# LCD_Dev_SCH_1.net
KiCad netlist of a schematic drawn in Altium Designer
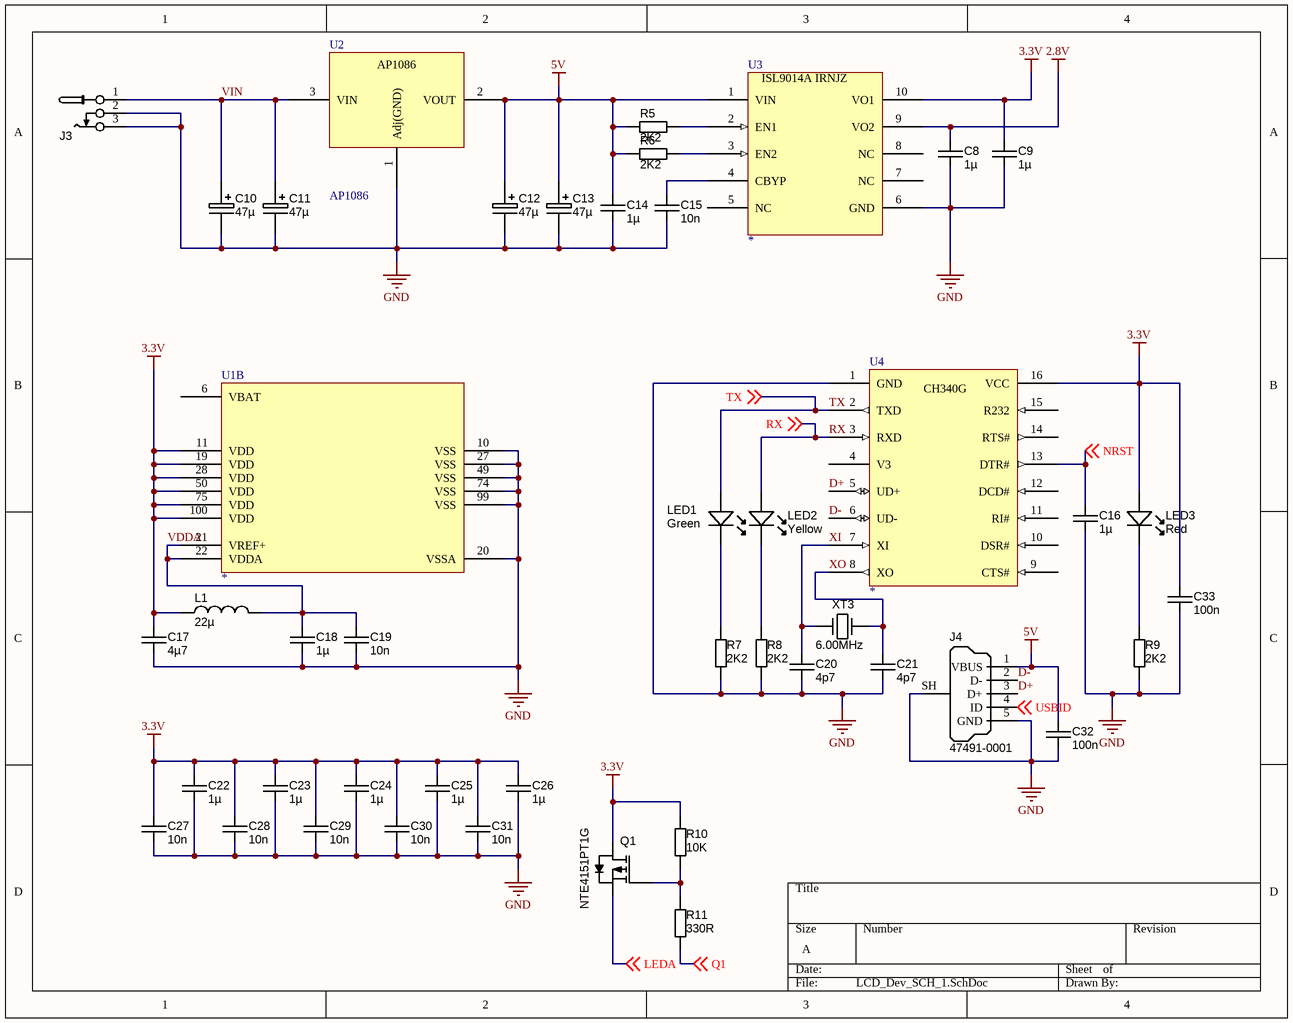
[diagram p0: LCD_Dev_SCH_1.SchDoc]

(export (version "E")
  (design (tool "Eeschema 10.0.6"))
  (components
    (comp (ref "C8")
      (value "1µ")
      (footprint "CAPC2012X135N")
      (description "Capacitor SMD Cer 1uF 10% 16V X7R 0805")
      (fields (field (name "TOLERANCE") "±10%") (field (name "Comment") "approved sub OK"))
      (libsource (lib "PBL - Capacitors") (part "CAPC_1u_0805_X7R_16V_10%"))
    )
    (comp (ref "C9")
      (value "1µ")
      (footprint "CAPC2012X135N")
      (description "Capacitor SMD Cer 1uF 10% 16V X7R 0805")
      (fields (field (name "TOLERANCE") "±10%") (field (name "Comment") "approved sub OK"))
      (libsource (lib "PBL - Capacitors") (part "CAPC_1u_0805_X7R_16V_10%"))
    )
    (comp (ref "C10")
      (value "47µ")
      (footprint "CAPMP6032X280N")
      (description "Capacitor SMD Tantalum 47uF 10% 16V 6032-28")
      (fields (field (name "TOLERANCE") "±10%"))
      (libsource (lib "PBL - Capacitors") (part "CAPT_47u_6032_16V"))
    )
    (comp (ref "C11")
      (value "47µ")
      (footprint "CAPMP6032X280N")
      (description "Capacitor SMD Tantalum 47uF 10% 16V 6032-28")
      (fields (field (name "TOLERANCE") "±10%"))
      (libsource (lib "PBL - Capacitors") (part "CAPT_47u_6032_16V"))
    )
    (comp (ref "C12")
      (value "47µ")
      (footprint "CAPMP6032X280N")
      (description "Capacitor SMD Tantalum 47uF 10% 16V 6032-28")
      (fields (field (name "TOLERANCE") "±10%"))
      (libsource (lib "PBL - Capacitors") (part "CAPT_47u_6032_16V"))
    )
    (comp (ref "C13")
      (value "47µ")
      (footprint "CAPMP6032X280N")
      (description "Capacitor SMD Tantalum 47uF 10% 16V 6032-28")
      (fields (field (name "TOLERANCE") "±10%"))
      (libsource (lib "PBL - Capacitors") (part "CAPT_47u_6032_16V"))
    )
    (comp (ref "C14")
      (value "1µ")
      (footprint "CAPC2012X135N")
      (description "Capacitor SMD Cer 1uF 10% 16V X7R 0805")
      (fields (field (name "TOLERANCE") "±10%") (field (name "Comment") "approved sub OK"))
      (libsource (lib "PBL - Capacitors") (part "CAPC_1u_0805_X7R_16V_10%"))
    )
    (comp (ref "C15")
      (value "10n")
      (footprint "CAPC1608X90N")
      (description "Capacitor SMD Cer 10nF 10% 50V X7R 0603")
      (fields (field (name "TOLERANCE") "±10%") (field (name "Comment") "approved sub OK"))
      (libsource (lib "PBL - Capacitors") (part "CAPC_10n_0603_X7R_50V_10%"))
    )
    (comp (ref "C16")
      (value "1µ")
      (footprint "CAPC2012X135N")
      (description "Capacitor SMD Cer 1uF 10% 16V X7R 0805")
      (fields (field (name "TOLERANCE") "±10%") (field (name "Comment") "approved sub OK"))
      (libsource (lib "PBL - Capacitors") (part "CAPC_1u_0805_X7R_16V_10%"))
    )
    (comp (ref "C17")
      (value "4µ7")
      (footprint "CAPC2012X135N")
      (description "Capacitor SMD Cer 4.7uF 10% 16V X5R 0805")
      (fields (field (name "TOLERANCE") "±10%") (field (name "Comment") "approved sub OK"))
      (libsource (lib "PBL - Capacitors") (part "CAPC_4u7_0805"))
    )
    (comp (ref "C18")
      (value "1µ")
      (footprint "CAPC2012X135N")
      (description "Capacitor SMD Cer 1uF 10% 16V X7R 0805")
      (fields (field (name "TOLERANCE") "±10%") (field (name "Comment") "approved sub OK"))
      (libsource (lib "PBL - Capacitors") (part "CAPC_1u_0805_X7R_16V_10%"))
    )
    (comp (ref "C19")
      (value "10n")
      (footprint "CAPC1608X90N")
      (description "Capacitor SMD Cer 10nF 10% 50V X7R 0603")
      (fields (field (name "TOLERANCE") "±10%") (field (name "Comment") "approved sub OK"))
      (libsource (lib "PBL - Capacitors") (part "CAPC_10n_0603_X7R_50V_10%"))
    )
    (comp (ref "C20")
      (value "4p7")
      (footprint "CAPC1608X90N")
      (description "Capacitor SMD Cer 4.7pF ±0.25pF 100V NP0 0603")
      (fields (field (name "TOLERANCE") "±0.25pF") (field (name "Comment") "approved sub OK"))
      (libsource (lib "PBL - Capacitors") (part "CAPC_4p7_100V_0603"))
    )
    (comp (ref "C21")
      (value "4p7")
      (footprint "CAPC1608X90N")
      (description "Capacitor SMD Cer 4.7pF ±0.25pF 100V NP0 0603")
      (fields (field (name "TOLERANCE") "±0.25pF") (field (name "Comment") "approved sub OK"))
      (libsource (lib "PBL - Capacitors") (part "CAPC_4p7_100V_0603"))
    )
    (comp (ref "C22")
      (value "1µ")
      (footprint "CAPC2012X135N")
      (description "Capacitor SMD Cer 1uF 10% 16V X7R 0805")
      (fields (field (name "TOLERANCE") "±10%") (field (name "Comment") "approved sub OK"))
      (libsource (lib "PBL - Capacitors") (part "CAPC_1u_0805_X7R_16V_10%"))
    )
    (comp (ref "C23")
      (value "1µ")
      (footprint "CAPC2012X135N")
      (description "Capacitor SMD Cer 1uF 10% 16V X7R 0805")
      (fields (field (name "TOLERANCE") "±10%") (field (name "Comment") "approved sub OK"))
      (libsource (lib "PBL - Capacitors") (part "CAPC_1u_0805_X7R_16V_10%"))
    )
    (comp (ref "C24")
      (value "1µ")
      (footprint "CAPC2012X135N")
      (description "Capacitor SMD Cer 1uF 10% 16V X7R 0805")
      (fields (field (name "TOLERANCE") "±10%") (field (name "Comment") "approved sub OK"))
      (libsource (lib "PBL - Capacitors") (part "CAPC_1u_0805_X7R_16V_10%"))
    )
    (comp (ref "C25")
      (value "1µ")
      (footprint "CAPC2012X135N")
      (description "Capacitor SMD Cer 1uF 10% 16V X7R 0805")
      (fields (field (name "TOLERANCE") "±10%") (field (name "Comment") "approved sub OK"))
      (libsource (lib "PBL - Capacitors") (part "CAPC_1u_0805_X7R_16V_10%"))
    )
    (comp (ref "C26")
      (value "1µ")
      (footprint "CAPC2012X135N")
      (description "Capacitor SMD Cer 1uF 10% 16V X7R 0805")
      (fields (field (name "TOLERANCE") "±10%") (field (name "Comment") "approved sub OK"))
      (libsource (lib "PBL - Capacitors") (part "CAPC_1u_0805_X7R_16V_10%"))
    )
    (comp (ref "C27")
      (value "10n")
      (footprint "CAPC1608X90N")
      (description "Capacitor SMD Cer 10nF 10% 50V X7R 0603")
      (fields (field (name "TOLERANCE") "±10%") (field (name "Comment") "approved sub OK"))
      (libsource (lib "PBL - Capacitors") (part "CAPC_10n_0603_X7R_50V_10%"))
    )
    (comp (ref "C28")
      (value "10n")
      (footprint "CAPC1608X90N")
      (description "Capacitor SMD Cer 10nF 10% 50V X7R 0603")
      (fields (field (name "TOLERANCE") "±10%") (field (name "Comment") "approved sub OK"))
      (libsource (lib "PBL - Capacitors") (part "CAPC_10n_0603_X7R_50V_10%"))
    )
    (comp (ref "C29")
      (value "10n")
      (footprint "CAPC1608X90N")
      (description "Capacitor SMD Cer 10nF 10% 50V X7R 0603")
      (fields (field (name "TOLERANCE") "±10%") (field (name "Comment") "approved sub OK"))
      (libsource (lib "PBL - Capacitors") (part "CAPC_10n_0603_X7R_50V_10%"))
    )
    (comp (ref "C30")
      (value "10n")
      (footprint "CAPC1608X90N")
      (description "Capacitor SMD Cer 10nF 10% 50V X7R 0603")
      (fields (field (name "TOLERANCE") "±10%") (field (name "Comment") "approved sub OK"))
      (libsource (lib "PBL - Capacitors") (part "CAPC_10n_0603_X7R_50V_10%"))
    )
    (comp (ref "C31")
      (value "10n")
      (footprint "CAPC1608X90N")
      (description "Capacitor SMD Cer 10nF 10% 50V X7R 0603")
      (fields (field (name "TOLERANCE") "±10%") (field (name "Comment") "approved sub OK"))
      (libsource (lib "PBL - Capacitors") (part "CAPC_10n_0603_X7R_50V_10%"))
    )
    (comp (ref "C32")
      (value "100n")
      (footprint "CAPC1608X90N")
      (description "Capacitor SMD Cer 100nF 10% 50V X7R 0603")
      (fields (field (name "TOLERANCE") "±10%") (field (name "Comment") "approved sub OK"))
      (libsource (lib "PBL - Capacitors") (part "CAPC_100n_0603_X7R_50V_10%"))
    )
    (comp (ref "C33")
      (value "100n")
      (footprint "CAPC1608X90N")
      (description "Capacitor SMD Cer 100nF 10% 50V X7R 0603")
      (fields (field (name "TOLERANCE") "±10%") (field (name "Comment") "approved sub OK"))
      (libsource (lib "PBL - Capacitors") (part "CAPC_100n_0603_X7R_50V_10%"))
    )
    (comp (ref "J3")
      (value "*")
      (footprint "CONN_PWR_JACK_0.7x2.35mm")
      (description "Connector Power THT 0.7mm ID x 2.35mm OD")
      (libsource (lib "PBL - Connectors") (part "CONN_PWR_JACK_0.7x2.35mm"))
    )
    (comp (ref "J4")
      (value "USB Micro Type B")
      (footprint "USB_Micro-B_Molex_SMD")
      (description "Connector SMD USB Micro Type B middle mount")
      (fields (field (name "MANUFACTURER PART NUMBER 1") "47491-0001"))
      (libsource (lib "PBL - Connectors") (part "USB_Micro_TypeB"))
    )
    (comp (ref "L1")
      (value "22µ")
      (footprint "INDM3225X240N")
      (description "Inductor 22uH 110mA 1210 SMD chip")
      (fields (field (name "TOLERANCE") "±10%") (field (name "Comment") "SMD-322522"))
      (libsource (lib "PBL - Inductors") (part "INDC_22u_1210_110mA"))
    )
    (comp (ref "LED1")
      (value "Green")
      (footprint "LED-0603-GREEN")
      (description "LED 0603 SMD Green 570nm 50mcd 20mA")
      (libsource (lib "PBL - Light Sources") (part "LED_SMD_Green_0603_570nm"))
    )
    (comp (ref "LED2")
      (value "Yellow")
      (footprint "LED-0603-YELLOW")
      (description "LED 0603 SMD Yellow 590nm 150mcd 20mA")
      (libsource (lib "PBL - Light Sources") (part "LED_SMD_Yellow_0603_150mcd"))
    )
    (comp (ref "LED3")
      (value "Red")
      (footprint "LED-0603-RED")
      (description "LED 0603 SMD Hyper Red 630nm 220mcd 20mA")
      (libsource (lib "PBL - Light Sources") (part "LED_SMD_Red_0603_220mcd"))
    )
    (comp (ref "Q1")
      (value "P-Channel")
      (footprint "SOT523F")
      (description "MOSFET SMD P-CH 20V 0.76A 0.313W SOT523F")
      (fields (field (name "MANUFACTURER PART NUMBER 1") "NTE4151PT1G"))
      (libsource (lib "PBL - Transistors") (part "MOSFET_P-CH_NTE4151PT1G"))
    )
    (comp (ref "R5")
      (value "2K2")
      (footprint "RESC1608X55N")
      (description "Resistor SMD chip 2.2k Ohm 0.1W 5% 0603")
      (fields (field (name "TOLERANCE") "±5%") (field (name "Comment") "Thick Film"))
      (libsource (lib "PBL - Resistors") (part "RES_2K2_0603_5%"))
    )
    (comp (ref "R6")
      (value "2K2")
      (footprint "RESC1608X55N")
      (description "Resistor SMD chip 2.2k Ohm 0.1W 5% 0603")
      (fields (field (name "TOLERANCE") "±5%") (field (name "Comment") "Thick Film"))
      (libsource (lib "PBL - Resistors") (part "RES_2K2_0603_5%"))
    )
    (comp (ref "R7")
      (value "2K2")
      (footprint "RESC1608X55N")
      (description "Resistor SMD chip 2.2k Ohm 0.1W 5% 0603")
      (fields (field (name "TOLERANCE") "±5%") (field (name "Comment") "Thick Film"))
      (libsource (lib "") (part "RES_2K2_0603_5%_1"))
    )
    (comp (ref "R8")
      (value "2K2")
      (footprint "RESC1608X55N")
      (description "Resistor SMD chip 2.2k Ohm 0.1W 5% 0603")
      (fields (field (name "TOLERANCE") "±5%") (field (name "Comment") "Thick Film"))
      (libsource (lib "") (part "RES_2K2_0603_5%_1"))
    )
    (comp (ref "R9")
      (value "2K2")
      (footprint "RESC1608X55N")
      (description "Resistor SMD chip 2.2k Ohm 0.1W 5% 0603")
      (fields (field (name "TOLERANCE") "±5%") (field (name "Comment") "Thick Film"))
      (libsource (lib "") (part "RES_2K2_0603_5%_1"))
    )
    (comp (ref "R10")
      (value "10K")
      (footprint "RESC1608X55N")
      (description "Resistor SMD chip 10k Ohm 0.1W 5% 0603")
      (fields (field (name "TOLERANCE") "±5%") (field (name "Comment") "Thick Film"))
      (libsource (lib "PBL - Resistors") (part "RES_10K_0603_5%"))
    )
    (comp (ref "R11")
      (value "330R")
      (footprint "RESC1608X55N")
      (description "Resistor SMD chip 330 Ohm 0.1W 5% 0603")
      (fields (field (name "TOLERANCE") "±5%") (field (name "Comment") "Thick Film"))
      (libsource (lib "PBL - Resistors") (part "RES_330R_0603_5%"))
    )
    (comp (ref "U1")
      (value "*")
      (footprint "LQFP100_STM32F4")
      (description "STM32F413VHT symbol for FSMC application with designated FSMC relevant pins")
      (libsource (lib "co2_meter_integrated_library") (part "STM32F413xH"))
    )
    (comp (ref "U2")
      (value "AP1086")
      (footprint "TO263-3L")
      (libsource (lib "co2_meter_integrated_library") (part "AP1086"))
    )
    (comp (ref "U3")
      (value "*")
      (footprint "10LD3X3DFN")
      (description "ISL9014A IRNJZ, Dual LDO, 3.3V and 2.8V, 300mA on both outputs")
      (libsource (lib "co2_meter_integrated_library") (part "ISL9014A_IRNJZ"))
    )
    (comp (ref "U4")
      (value "*")
      (footprint "SOP16")
      (description "USB bus conversion chip")
      (libsource (lib "co2_meter_integrated_library") (part "CH340G"))
    )
    (comp (ref "XT3")
      (value "6.00MHz")
      (footprint "CRYSTAL_HC49-US-SM")
      (description "Resonator Ceramic 6.00 MHz 30ppm")
      (libsource (lib "PBL - Resonators") (part "Crystal_6MHz_HC49/US"))
    )
  )
  (nets
    (net (code "1") (name "/D+") (class "Default")
      (node (ref "J4") (pin "3") (pinfunction "D+_3") (pintype "passive"))
      (node (ref "U4") (pin "5") (pinfunction "UD+_5") (pintype "bidirectional"))
    )
    (net (code "2") (name "/D-") (class "Default")
      (node (ref "J4") (pin "2") (pinfunction "D-_2") (pintype "passive"))
      (node (ref "U4") (pin "6") (pinfunction "UD-_6") (pintype "bidirectional"))
    )
    (net (code "3") (name "/VDDA") (class "Default")
      (node (ref "C18") (pin "1") (pintype "passive"))
      (node (ref "C19") (pin "1") (pintype "passive"))
      (node (ref "L1") (pin "2") (pinfunction "2_2") (pintype "passive"))
      (node (ref "U1") (pin "21") (pinfunction "VREF+_21") (pintype "power_in"))
      (node (ref "U1") (pin "22") (pinfunction "VDDA_22") (pintype "power_in"))
    )
    (net (code "4") (name "/VIN") (class "Default")
      (node (ref "C10") (pin "1") (pintype "passive"))
      (node (ref "C11") (pin "1") (pintype "passive"))
      (node (ref "J3") (pin "1") (pinfunction "POS_1") (pintype "passive"))
      (node (ref "U2") (pin "3") (pinfunction "VIN_3") (pintype "power_in"))
    )
    (net (code "5") (name "/XI") (class "Default")
      (node (ref "C20") (pin "1") (pintype "passive"))
      (node (ref "U4") (pin "7") (pinfunction "XI_7") (pintype "input"))
      (node (ref "XT3") (pin "1") (pinfunction "IN_1") (pintype "passive"))
    )
    (net (code "6") (name "/XO") (class "Default")
      (node (ref "C21") (pin "1") (pintype "passive"))
      (node (ref "U4") (pin "8") (pinfunction "XO_8") (pintype "output"))
      (node (ref "XT3") (pin "2") (pinfunction "OUT_2") (pintype "passive"))
    )
    (net (code "7") (name "2.8V") (class "Default")
      (node (ref "C8") (pin "1") (pintype "passive"))
      (node (ref "U3") (pin "9") (pinfunction "VO2_9") (pintype "power_in"))
    )
    (net (code "8") (name "3.3V") (class "Default")
      (node (ref "C17") (pin "1") (pintype "passive"))
      (node (ref "C22") (pin "1") (pintype "passive"))
      (node (ref "C23") (pin "1") (pintype "passive"))
      (node (ref "C24") (pin "1") (pintype "passive"))
      (node (ref "C25") (pin "1") (pintype "passive"))
      (node (ref "C26") (pin "1") (pintype "passive"))
      (node (ref "C27") (pin "1") (pintype "passive"))
      (node (ref "C28") (pin "1") (pintype "passive"))
      (node (ref "C29") (pin "1") (pintype "passive"))
      (node (ref "C30") (pin "1") (pintype "passive"))
      (node (ref "C31") (pin "1") (pintype "passive"))
      (node (ref "C33") (pin "1") (pintype "passive"))
      (node (ref "C9") (pin "1") (pintype "passive"))
      (node (ref "L1") (pin "1") (pinfunction "1_1") (pintype "passive"))
      (node (ref "LED3") (pin "A") (pinfunction "A_A") (pintype "passive"))
      (node (ref "Q1") (pin "3") (pinfunction "D_3") (pintype "passive"))
      (node (ref "R10") (pin "1") (pinfunction "1_1") (pintype "passive"))
      (node (ref "U1") (pin "100") (pinfunction "VDD_100") (pintype "power_in"))
      (node (ref "U1") (pin "11") (pinfunction "VDD_11") (pintype "power_in"))
      (node (ref "U1") (pin "19") (pinfunction "VDD_19") (pintype "power_in"))
      (node (ref "U1") (pin "28") (pinfunction "VDD_28") (pintype "power_in"))
      (node (ref "U1") (pin "50") (pinfunction "VDD_50") (pintype "power_in"))
      (node (ref "U1") (pin "75") (pinfunction "VDD_75") (pintype "power_in"))
      (node (ref "U3") (pin "10") (pinfunction "VO1_10") (pintype "power_in"))
      (node (ref "U4") (pin "16") (pinfunction "VCC_16") (pintype "power_in"))
    )
    (net (code "9") (name "5V") (class "Default")
      (node (ref "C12") (pin "1") (pintype "passive"))
      (node (ref "C13") (pin "1") (pintype "passive"))
      (node (ref "C14") (pin "1") (pintype "passive"))
      (node (ref "C32") (pin "1") (pintype "passive"))
      (node (ref "J4") (pin "1") (pinfunction "VBUS_1") (pintype "passive"))
      (node (ref "R5") (pin "1") (pinfunction "1_1") (pintype "passive"))
      (node (ref "R6") (pin "1") (pinfunction "1_1") (pintype "passive"))
      (node (ref "U2") (pin "2") (pinfunction "VOUT_2") (pintype "power_in"))
      (node (ref "U3") (pin "1") (pinfunction "VIN_1") (pintype "power_in"))
    )
    (net (code "10") (name "GND") (class "Default")
      (node (ref "C10") (pin "2") (pintype "passive"))
      (node (ref "C11") (pin "2") (pintype "passive"))
      (node (ref "C12") (pin "2") (pintype "passive"))
      (node (ref "C13") (pin "2") (pintype "passive"))
      (node (ref "C14") (pin "2") (pintype "passive"))
      (node (ref "C15") (pin "2") (pintype "passive"))
      (node (ref "C16") (pin "2") (pintype "passive"))
      (node (ref "C17") (pin "2") (pintype "passive"))
      (node (ref "C18") (pin "2") (pintype "passive"))
      (node (ref "C19") (pin "2") (pintype "passive"))
      (node (ref "C20") (pin "2") (pintype "passive"))
      (node (ref "C21") (pin "2") (pintype "passive"))
      (node (ref "C22") (pin "2") (pintype "passive"))
      (node (ref "C23") (pin "2") (pintype "passive"))
      (node (ref "C24") (pin "2") (pintype "passive"))
      (node (ref "C25") (pin "2") (pintype "passive"))
      (node (ref "C26") (pin "2") (pintype "passive"))
      (node (ref "C27") (pin "2") (pintype "passive"))
      (node (ref "C28") (pin "2") (pintype "passive"))
      (node (ref "C29") (pin "2") (pintype "passive"))
      (node (ref "C30") (pin "2") (pintype "passive"))
      (node (ref "C31") (pin "2") (pintype "passive"))
      (node (ref "C32") (pin "2") (pintype "passive"))
      (node (ref "C33") (pin "2") (pintype "passive"))
      (node (ref "C8") (pin "2") (pintype "passive"))
      (node (ref "C9") (pin "2") (pintype "passive"))
      (node (ref "J3") (pin "2") (pinfunction "NC_2") (pintype "passive"))
      (node (ref "J3") (pin "3") (pinfunction "NEG_3") (pintype "passive"))
      (node (ref "J4") (pin "5") (pinfunction "GND_5") (pintype "passive"))
      (node (ref "J4") (pin "SH") (pinfunction "Shell_SH") (pintype "passive"))
      (node (ref "R7") (pin "2") (pinfunction "2_2") (pintype "passive"))
      (node (ref "R8") (pin "2") (pinfunction "2_2") (pintype "passive"))
      (node (ref "R9") (pin "2") (pinfunction "2_2") (pintype "passive"))
      (node (ref "U1") (pin "10") (pinfunction "VSS_10") (pintype "power_in"))
      (node (ref "U1") (pin "20") (pinfunction "VSSA_20") (pintype "power_in"))
      (node (ref "U1") (pin "27") (pinfunction "VSS_27") (pintype "power_in"))
      (node (ref "U1") (pin "49") (pinfunction "VSS_49") (pintype "power_in"))
      (node (ref "U1") (pin "74") (pinfunction "VSS_74") (pintype "power_in"))
      (node (ref "U1") (pin "99") (pinfunction "VSS_99") (pintype "power_in"))
      (node (ref "U2") (pin "1") (pinfunction "Adj(GND)_1") (pintype "power_in"))
      (node (ref "U3") (pin "6") (pinfunction "GND_6") (pintype "power_in"))
      (node (ref "U4") (pin "1") (pinfunction "GND_1") (pintype "power_in"))
    )
    (net (code "11") (name "LEDA") (class "Default")
      (node (ref "Q1") (pin "2") (pinfunction "S_2") (pintype "passive"))
    )
    (net (code "12") (name "NRST") (class "Default")
      (node (ref "C16") (pin "1") (pintype "passive"))
      (node (ref "U4") (pin "13") (pinfunction "DTR#_13") (pintype "output"))
    )
    (net (code "13") (name "Net-(LED1-PadK)") (class "Default")
      (node (ref "LED1") (pin "K") (pinfunction "K_K") (pintype "passive"))
      (node (ref "R7") (pin "1") (pinfunction "1_1") (pintype "passive"))
    )
    (net (code "14") (name "Net-(LED2-PadK)") (class "Default")
      (node (ref "LED2") (pin "K") (pinfunction "K_K") (pintype "passive"))
      (node (ref "R8") (pin "1") (pinfunction "1_1") (pintype "passive"))
    )
    (net (code "15") (name "Net-(LED3-PadK)") (class "Default")
      (node (ref "LED3") (pin "K") (pinfunction "K_K") (pintype "passive"))
      (node (ref "R9") (pin "1") (pinfunction "1_1") (pintype "passive"))
    )
    (net (code "16") (name "Net-(Q1-G)") (class "Default")
      (node (ref "Q1") (pin "1") (pinfunction "G_1") (pintype "passive"))
      (node (ref "R10") (pin "2") (pinfunction "2_2") (pintype "passive"))
      (node (ref "R11") (pin "1") (pinfunction "1_1") (pintype "passive"))
    )
    (net (code "17") (name "Net-(U3-CBYP)") (class "Default")
      (node (ref "C15") (pin "1") (pintype "passive"))
      (node (ref "U3") (pin "4") (pinfunction "CBYP_4") (pintype "power_in"))
    )
    (net (code "18") (name "Net-(U3-EN1)") (class "Default")
      (node (ref "R5") (pin "2") (pinfunction "2_2") (pintype "passive"))
      (node (ref "U3") (pin "2") (pinfunction "EN1_2") (pintype "input"))
    )
    (net (code "19") (name "Net-(U3-EN2)") (class "Default")
      (node (ref "R6") (pin "2") (pinfunction "2_2") (pintype "passive"))
      (node (ref "U3") (pin "3") (pinfunction "EN2_3") (pintype "input"))
    )
    (net (code "20") (name "Q1") (class "Default")
      (node (ref "R11") (pin "2") (pinfunction "2_2") (pintype "passive"))
    )
    (net (code "21") (name "RX") (class "Default")
      (node (ref "LED2") (pin "A") (pinfunction "A_A") (pintype "passive"))
      (node (ref "U4") (pin "3") (pinfunction "RXD_3") (pintype "input"))
    )
    (net (code "22") (name "TX") (class "Default")
      (node (ref "LED1") (pin "A") (pinfunction "A_A") (pintype "passive"))
      (node (ref "U4") (pin "2") (pinfunction "TXD_2") (pintype "output"))
    )
    (net (code "23") (name "USBID") (class "Default")
      (node (ref "J4") (pin "4") (pinfunction "ID_4") (pintype "passive"))
    )
    (net (code "24") (name "unconnected-(U1B-VBAT-Pad6)") (class "Default")
      (node (ref "U1") (pin "6") (pinfunction "VBAT_6") (pintype "power_in"))
    )
    (net (code "25") (name "unconnected-(U3-NC-Pad5)") (class "Default")
      (node (ref "U3") (pin "5") (pinfunction "NC_5") (pintype "passive"))
    )
    (net (code "26") (name "unconnected-(U3-NC-Pad7)") (class "Default")
      (node (ref "U3") (pin "7") (pinfunction "NC_7") (pintype "passive"))
    )
    (net (code "27") (name "unconnected-(U3-NC-Pad8)") (class "Default")
      (node (ref "U3") (pin "8") (pinfunction "NC_8") (pintype "passive"))
    )
    (net (code "28") (name "unconnected-(U4-CTS#-Pad9)") (class "Default")
      (node (ref "U4") (pin "9") (pinfunction "CTS#_9") (pintype "input"))
    )
    (net (code "29") (name "unconnected-(U4-DCD#-Pad12)") (class "Default")
      (node (ref "U4") (pin "12") (pinfunction "DCD#_12") (pintype "input"))
    )
    (net (code "30") (name "unconnected-(U4-DSR#-Pad10)") (class "Default")
      (node (ref "U4") (pin "10") (pinfunction "DSR#_10") (pintype "input"))
    )
    (net (code "31") (name "unconnected-(U4-R232-Pad15)") (class "Default")
      (node (ref "U4") (pin "15") (pinfunction "R232_15") (pintype "input"))
    )
    (net (code "32") (name "unconnected-(U4-RI#-Pad11)") (class "Default")
      (node (ref "U4") (pin "11") (pinfunction "RI#_11") (pintype "input"))
    )
    (net (code "33") (name "unconnected-(U4-RTS#-Pad14)") (class "Default")
      (node (ref "U4") (pin "14") (pinfunction "RTS#_14") (pintype "output"))
    )
    (net (code "34") (name "unconnected-(U4-V3-Pad4)") (class "Default")
      (node (ref "U4") (pin "4") (pinfunction "V3_4") (pintype "power_in"))
    )
  )
)
